# Gain_HPF.net
KiCad netlist of a schematic drawn in EAGLE
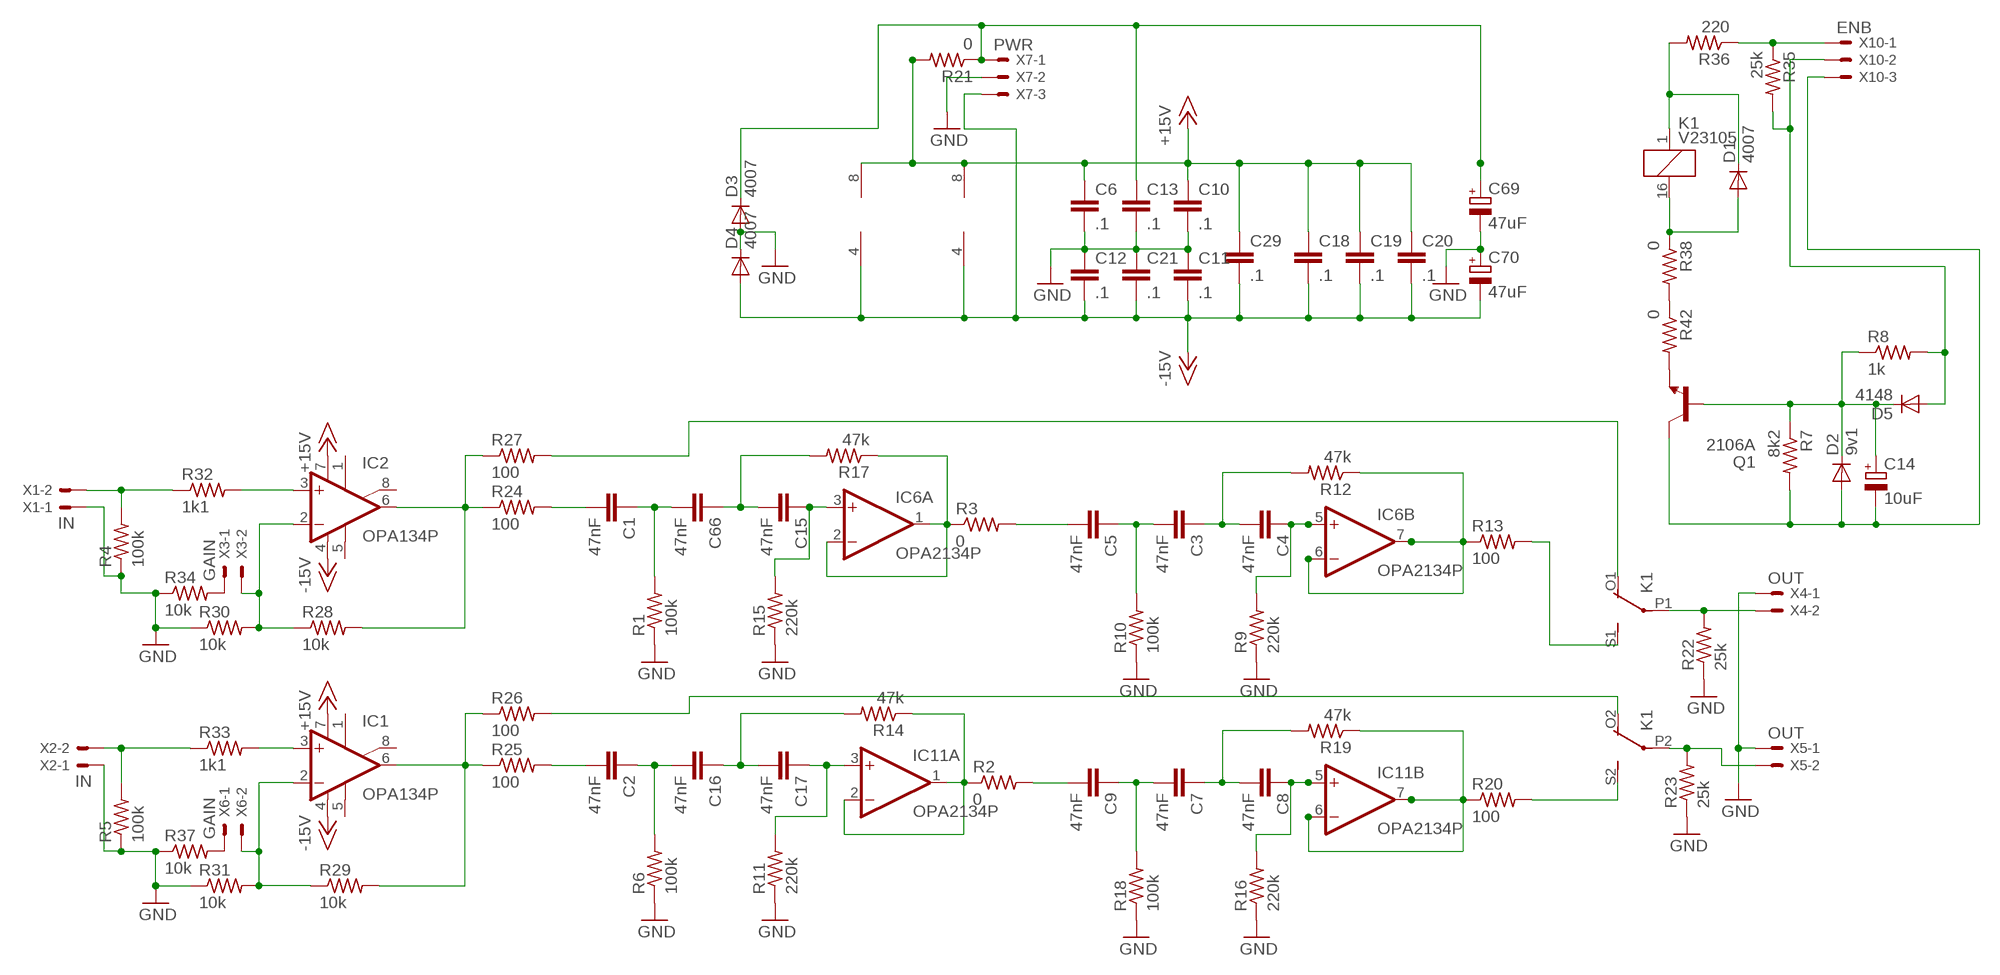
[diagram p0: schematic, sheet 1]

(export (version "E")
  (design (tool "Eeschema 10.0.6"))
  (components
    (comp (ref "C1")
      (value "47nF")
      (footprint "eagle-import:C050-075X075")
      (libsource (lib "eagle-import") (part "C-EU050-075X075"))
    )
    (comp (ref "C2")
      (value "47nF")
      (footprint "eagle-import:C050-075X075")
      (libsource (lib "eagle-import") (part "C-EU050-075X075"))
    )
    (comp (ref "C3")
      (value "47nF")
      (footprint "eagle-import:C050-075X075")
      (libsource (lib "eagle-import") (part "C-EU050-075X075"))
    )
    (comp (ref "C4")
      (value "47nF")
      (footprint "eagle-import:C050-075X075")
      (libsource (lib "eagle-import") (part "C-EU050-075X075"))
    )
    (comp (ref "C5")
      (value "47nF")
      (footprint "eagle-import:C050-075X075")
      (libsource (lib "eagle-import") (part "C-EU050-075X075"))
    )
    (comp (ref "C6")
      (value ".1")
      (footprint "eagle-import:C4532")
      (libsource (lib "eagle-import") (part "C-EUC4532"))
    )
    (comp (ref "C7")
      (value "47nF")
      (footprint "eagle-import:C050-075X075")
      (libsource (lib "eagle-import") (part "C-EU050-075X075"))
    )
    (comp (ref "C8")
      (value "47nF")
      (footprint "eagle-import:C050-075X075")
      (libsource (lib "eagle-import") (part "C-EU050-075X075"))
    )
    (comp (ref "C9")
      (value "47nF")
      (footprint "eagle-import:C050-075X075")
      (libsource (lib "eagle-import") (part "C-EU050-075X075"))
    )
    (comp (ref "C10")
      (value ".1")
      (footprint "eagle-import:C4532")
      (libsource (lib "eagle-import") (part "C-EUC4532"))
    )
    (comp (ref "C11")
      (value ".1")
      (footprint "eagle-import:C4532")
      (libsource (lib "eagle-import") (part "C-EUC4532"))
    )
    (comp (ref "C12")
      (value ".1")
      (footprint "eagle-import:C4532")
      (libsource (lib "eagle-import") (part "C-EUC4532"))
    )
    (comp (ref "C13")
      (value ".1")
      (footprint "eagle-import:C4532")
      (libsource (lib "eagle-import") (part "C-EUC4532"))
    )
    (comp (ref "C14")
      (value "10uF")
      (footprint "eagle-import:E2,5-6")
      (libsource (lib "eagle-import") (part "CPOL-EUE2.5-6"))
    )
    (comp (ref "C15")
      (value "47nF")
      (footprint "eagle-import:C050-075X075")
      (libsource (lib "eagle-import") (part "C-EU050-075X075"))
    )
    (comp (ref "C16")
      (value "47nF")
      (footprint "eagle-import:C050-075X075")
      (libsource (lib "eagle-import") (part "C-EU050-075X075"))
    )
    (comp (ref "C17")
      (value "47nF")
      (footprint "eagle-import:C050-075X075")
      (libsource (lib "eagle-import") (part "C-EU050-075X075"))
    )
    (comp (ref "C18")
      (value ".1")
      (footprint "eagle-import:C4532")
      (libsource (lib "eagle-import") (part "C-EUC4532"))
    )
    (comp (ref "C19")
      (value ".1")
      (footprint "eagle-import:C4532")
      (libsource (lib "eagle-import") (part "C-EUC4532"))
    )
    (comp (ref "C20")
      (value ".1")
      (footprint "eagle-import:C4532")
      (libsource (lib "eagle-import") (part "C-EUC4532"))
    )
    (comp (ref "C21")
      (value ".1")
      (footprint "eagle-import:C4532")
      (libsource (lib "eagle-import") (part "C-EUC4532"))
    )
    (comp (ref "C29")
      (value ".1")
      (footprint "eagle-import:C4532")
      (libsource (lib "eagle-import") (part "C-EUC4532"))
    )
    (comp (ref "C66")
      (value "47nF")
      (footprint "eagle-import:C050-075X075")
      (libsource (lib "eagle-import") (part "C-EU050-075X075"))
    )
    (comp (ref "C69")
      (value "47uF")
      (footprint "eagle-import:E2,5-7")
      (libsource (lib "eagle-import") (part "CPOL-EUE2.5-7"))
    )
    (comp (ref "C70")
      (value "47uF")
      (footprint "eagle-import:E2,5-7")
      (libsource (lib "eagle-import") (part "CPOL-EUE2.5-7"))
    )
    (comp (ref "D1")
      (value "4007")
      (footprint "eagle-import:DO35-7")
      (libsource (lib "eagle-import") (part "1N4148DO35-7"))
    )
    (comp (ref "D2")
      (value "9v1")
      (footprint "eagle-import:DO35-7")
      (libsource (lib "eagle-import") (part "1N4148DO35-7"))
    )
    (comp (ref "D3")
      (value "4007")
      (footprint "eagle-import:DO35-10")
      (libsource (lib "eagle-import") (part "1N4148DO35-10"))
    )
    (comp (ref "D4")
      (value "4007")
      (footprint "eagle-import:DO35-10")
      (libsource (lib "eagle-import") (part "1N4148DO35-10"))
    )
    (comp (ref "D5")
      (value "4148")
      (footprint "eagle-import:DO35-7")
      (libsource (lib "eagle-import") (part "1N4148DO35-7"))
    )
    (comp (ref "IC1")
      (value "OPA134P")
      (footprint "eagle-import:DIL08")
      (libsource (lib "eagle-import") (part "OPA134P"))
    )
    (comp (ref "IC2")
      (value "OPA134P")
      (footprint "eagle-import:DIL08")
      (libsource (lib "eagle-import") (part "OPA134P"))
    )
    (comp (ref "IC6")
      (value "OPA2134P")
      (footprint "eagle-import:DIL08")
      (libsource (lib "eagle-import") (part "OPA2134P"))
    )
    (comp (ref "IC11")
      (value "OPA2134P")
      (footprint "eagle-import:DIL08")
      (libsource (lib "eagle-import") (part "OPA2134P"))
    )
    (comp (ref "K1")
      (value "V23105")
      (footprint "eagle-import:351")
      (libsource (lib "eagle-import") (part "351"))
    )
    (comp (ref "Q1")
      (value "2106A")
      (footprint "eagle-import:TO92-EBC")
      (libsource (lib "eagle-import") (part "BC546B"))
    )
    (comp (ref "R1")
      (value "100k")
      (footprint "eagle-import:0309_10")
      (libsource (lib "eagle-import") (part "R-US_0309/10"))
    )
    (comp (ref "R2")
      (value "0")
      (footprint "eagle-import:0309_10")
      (libsource (lib "eagle-import") (part "R-US_0309/10"))
    )
    (comp (ref "R3")
      (value "0")
      (footprint "eagle-import:0309_12")
      (libsource (lib "eagle-import") (part "R-US_0309/12"))
    )
    (comp (ref "R4")
      (value "100k")
      (footprint "eagle-import:0309_12")
      (libsource (lib "eagle-import") (part "R-US_0309/12"))
    )
    (comp (ref "R5")
      (value "100k")
      (footprint "eagle-import:0309_12")
      (libsource (lib "eagle-import") (part "R-US_0309/12"))
    )
    (comp (ref "R6")
      (value "100k")
      (footprint "eagle-import:0309_10")
      (libsource (lib "eagle-import") (part "R-US_0309/10"))
    )
    (comp (ref "R7")
      (value "8k2")
      (footprint "eagle-import:R1210")
      (libsource (lib "eagle-import") (part "R-US_R1210"))
    )
    (comp (ref "R8")
      (value "1k")
      (footprint "eagle-import:R1210")
      (libsource (lib "eagle-import") (part "R-US_R1210"))
    )
    (comp (ref "R9")
      (value "220k")
      (footprint "eagle-import:0309_10")
      (libsource (lib "eagle-import") (part "R-US_0309/10"))
    )
    (comp (ref "R10")
      (value "100k")
      (footprint "eagle-import:0309_10")
      (libsource (lib "eagle-import") (part "R-US_0309/10"))
    )
    (comp (ref "R11")
      (value "220k")
      (footprint "eagle-import:0309_10")
      (libsource (lib "eagle-import") (part "R-US_0309/10"))
    )
    (comp (ref "R12")
      (value "47k")
      (footprint "eagle-import:0309_10")
      (libsource (lib "eagle-import") (part "R-US_0309/10"))
    )
    (comp (ref "R13")
      (value "100")
      (footprint "eagle-import:0309_10")
      (libsource (lib "eagle-import") (part "R-US_0309/10"))
    )
    (comp (ref "R14")
      (value "47k")
      (footprint "eagle-import:0309_10")
      (libsource (lib "eagle-import") (part "R-US_0309/10"))
    )
    (comp (ref "R15")
      (value "220k")
      (footprint "eagle-import:0309_10")
      (libsource (lib "eagle-import") (part "R-US_0309/10"))
    )
    (comp (ref "R16")
      (value "220k")
      (footprint "eagle-import:0309_10")
      (libsource (lib "eagle-import") (part "R-US_0309/10"))
    )
    (comp (ref "R17")
      (value "47k")
      (footprint "eagle-import:0309_10")
      (libsource (lib "eagle-import") (part "R-US_0309/10"))
    )
    (comp (ref "R18")
      (value "100k")
      (footprint "eagle-import:0309_10")
      (libsource (lib "eagle-import") (part "R-US_0309/10"))
    )
    (comp (ref "R19")
      (value "47k")
      (footprint "eagle-import:0309_10")
      (libsource (lib "eagle-import") (part "R-US_0309/10"))
    )
    (comp (ref "R20")
      (value "100")
      (footprint "eagle-import:0309_10")
      (libsource (lib "eagle-import") (part "R-US_0309/10"))
    )
    (comp (ref "R21")
      (value "0")
      (footprint "eagle-import:0309_10")
      (libsource (lib "eagle-import") (part "R-US_0309/10"))
    )
    (comp (ref "R22")
      (value "25k")
      (footprint "eagle-import:0309_10")
      (libsource (lib "eagle-import") (part "R-US_0309/10"))
    )
    (comp (ref "R23")
      (value "25k")
      (footprint "eagle-import:0309_10")
      (libsource (lib "eagle-import") (part "R-US_0309/10"))
    )
    (comp (ref "R24")
      (value "100")
      (footprint "eagle-import:0309_12")
      (libsource (lib "eagle-import") (part "R-US_0309/12"))
    )
    (comp (ref "R25")
      (value "100")
      (footprint "eagle-import:0309_12")
      (libsource (lib "eagle-import") (part "R-US_0309/12"))
    )
    (comp (ref "R26")
      (value "100")
      (footprint "eagle-import:0309_10")
      (libsource (lib "eagle-import") (part "R-US_0309/10"))
    )
    (comp (ref "R27")
      (value "100")
      (footprint "eagle-import:0309_10")
      (libsource (lib "eagle-import") (part "R-US_0309/10"))
    )
    (comp (ref "R28")
      (value "10k")
      (footprint "eagle-import:0309_10")
      (libsource (lib "eagle-import") (part "R-US_0309/10"))
    )
    (comp (ref "R29")
      (value "10k")
      (footprint "eagle-import:0309_10")
      (libsource (lib "eagle-import") (part "R-US_0309/10"))
    )
    (comp (ref "R30")
      (value "10k")
      (footprint "eagle-import:0309_10")
      (libsource (lib "eagle-import") (part "R-US_0309/10"))
    )
    (comp (ref "R31")
      (value "10k")
      (footprint "eagle-import:0309_10")
      (libsource (lib "eagle-import") (part "R-US_0309/10"))
    )
    (comp (ref "R32")
      (value "1k1")
      (footprint "eagle-import:0309_10")
      (libsource (lib "eagle-import") (part "R-US_0309/10"))
    )
    (comp (ref "R33")
      (value "1k1")
      (footprint "eagle-import:0309_10")
      (libsource (lib "eagle-import") (part "R-US_0309/10"))
    )
    (comp (ref "R34")
      (value "10k")
      (footprint "eagle-import:0309_10")
      (libsource (lib "eagle-import") (part "R-US_0309/10"))
    )
    (comp (ref "R35")
      (value "25k")
      (footprint "eagle-import:0309_10")
      (libsource (lib "eagle-import") (part "R-US_0309/10"))
    )
    (comp (ref "R36")
      (value "220")
      (footprint "eagle-import:0309_10")
      (libsource (lib "eagle-import") (part "R-US_0309/10"))
    )
    (comp (ref "R37")
      (value "10k")
      (footprint "eagle-import:0309_10")
      (libsource (lib "eagle-import") (part "R-US_0309/10"))
    )
    (comp (ref "R38")
      (value "0")
      (footprint "eagle-import:0309_10")
      (libsource (lib "eagle-import") (part "R-US_0309/10"))
    )
    (comp (ref "R42")
      (value "0")
      (footprint "eagle-import:0309_10")
      (libsource (lib "eagle-import") (part "R-US_0309/10"))
    )
    (comp (ref "X1")
      (value "IN")
      (footprint "eagle-import:22-23-2021")
      (fields (field (name "MF") "MOLEX") (field (name "MPN") "22-23-2021"))
      (libsource (lib "eagle-import") (part "22-23-2021"))
    )
    (comp (ref "X2")
      (value "IN")
      (footprint "eagle-import:22-23-2021")
      (fields (field (name "MF") "MOLEX") (field (name "MPN") "22-23-2021"))
      (libsource (lib "eagle-import") (part "22-23-2021"))
    )
    (comp (ref "X3")
      (value "GAIN")
      (footprint "eagle-import:22-23-2021")
      (fields (field (name "MF") "MOLEX") (field (name "MPN") "22-23-2021"))
      (libsource (lib "eagle-import") (part "22-23-2021"))
    )
    (comp (ref "X4")
      (value "OUT")
      (footprint "eagle-import:22-23-2021")
      (fields (field (name "MF") "MOLEX") (field (name "MPN") "22-23-2021"))
      (libsource (lib "eagle-import") (part "22-23-2021"))
    )
    (comp (ref "X5")
      (value "OUT")
      (footprint "eagle-import:22-23-2021")
      (fields (field (name "MF") "MOLEX") (field (name "MPN") "22-23-2021"))
      (libsource (lib "eagle-import") (part "22-23-2021"))
    )
    (comp (ref "X6")
      (value "GAIN")
      (footprint "eagle-import:22-23-2021")
      (fields (field (name "MF") "MOLEX") (field (name "MPN") "22-23-2021"))
      (libsource (lib "eagle-import") (part "22-23-2021"))
    )
    (comp (ref "X7")
      (value "PWR")
      (footprint "eagle-import:22-23-2031")
      (fields (field (name "MF") "MOLEX") (field (name "MPN") "22-23-2031"))
      (libsource (lib "eagle-import") (part "22-23-2031"))
    )
    (comp (ref "X10")
      (value "ENB")
      (footprint "eagle-import:22-23-2031")
      (fields (field (name "MF") "MOLEX") (field (name "MPN") "22-23-2031"))
      (libsource (lib "eagle-import") (part "22-23-2031"))
    )
  )
  (nets
    (net (code "1") (name "+15V") (class "Default")
      (node (ref "C10") (pin "1") (pinfunction "1_1") (pintype "passive"))
      (node (ref "C18") (pin "1") (pinfunction "1_1") (pintype "passive"))
      (node (ref "C19") (pin "1") (pinfunction "1_1") (pintype "passive"))
      (node (ref "C20") (pin "1") (pinfunction "1_1") (pintype "passive"))
      (node (ref "C29") (pin "1") (pinfunction "1_1") (pintype "passive"))
      (node (ref "C6") (pin "1") (pinfunction "1_1") (pintype "passive"))
      (node (ref "IC1") (pin "7") (pinfunction "V+_7") (pintype "power_in"))
      (node (ref "IC11") (pin "8") (pinfunction "V+_8") (pintype "power_in"))
      (node (ref "IC2") (pin "7") (pinfunction "V+_7") (pintype "power_in"))
      (node (ref "IC6") (pin "8") (pinfunction "V+_8") (pintype "power_in"))
      (node (ref "R21") (pin "2") (pinfunction "2_2") (pintype "passive"))
    )
    (net (code "2") (name "-15V") (class "Default")
      (node (ref "C11") (pin "2") (pinfunction "2_2") (pintype "passive"))
      (node (ref "C12") (pin "2") (pinfunction "2_2") (pintype "passive"))
      (node (ref "C18") (pin "2") (pinfunction "2_2") (pintype "passive"))
      (node (ref "C19") (pin "2") (pinfunction "2_2") (pintype "passive"))
      (node (ref "C20") (pin "2") (pinfunction "2_2") (pintype "passive"))
      (node (ref "C21") (pin "2") (pinfunction "2_2") (pintype "passive"))
      (node (ref "C29") (pin "2") (pinfunction "2_2") (pintype "passive"))
      (node (ref "C70") (pin "-") (pinfunction "-_-") (pintype "passive"))
      (node (ref "D4") (pin "A") (pinfunction "A_A") (pintype "passive"))
      (node (ref "IC1") (pin "4") (pinfunction "V-_4") (pintype "power_in"))
      (node (ref "IC11") (pin "4") (pinfunction "V-_4") (pintype "power_in"))
      (node (ref "IC2") (pin "4") (pinfunction "V-_4") (pintype "power_in"))
      (node (ref "IC6") (pin "4") (pinfunction "V-_4") (pintype "power_in"))
      (node (ref "X7") (pin "3") (pinfunction "S_3") (pintype "passive"))
    )
    (net (code "3") (name "GND") (class "Default")
      (node (ref "C10") (pin "2") (pinfunction "2_2") (pintype "passive"))
      (node (ref "C11") (pin "1") (pinfunction "1_1") (pintype "passive"))
      (node (ref "C12") (pin "1") (pinfunction "1_1") (pintype "passive"))
      (node (ref "C13") (pin "2") (pinfunction "2_2") (pintype "passive"))
      (node (ref "C21") (pin "1") (pinfunction "1_1") (pintype "passive"))
      (node (ref "C6") (pin "2") (pinfunction "2_2") (pintype "passive"))
      (node (ref "C69") (pin "-") (pinfunction "-_-") (pintype "passive"))
      (node (ref "C70") (pin "+") (pinfunction "+_+") (pintype "passive"))
      (node (ref "D3") (pin "A") (pinfunction "A_A") (pintype "passive"))
      (node (ref "D4") (pin "C") (pinfunction "C_C") (pintype "passive"))
      (node (ref "R1") (pin "1") (pinfunction "1_1") (pintype "passive"))
      (node (ref "R10") (pin "1") (pinfunction "1_1") (pintype "passive"))
      (node (ref "R11") (pin "1") (pinfunction "1_1") (pintype "passive"))
      (node (ref "R15") (pin "1") (pinfunction "1_1") (pintype "passive"))
      (node (ref "R16") (pin "1") (pinfunction "1_1") (pintype "passive"))
      (node (ref "R18") (pin "1") (pinfunction "1_1") (pintype "passive"))
      (node (ref "R22") (pin "1") (pinfunction "1_1") (pintype "passive"))
      (node (ref "R23") (pin "1") (pinfunction "1_1") (pintype "passive"))
      (node (ref "R30") (pin "1") (pinfunction "1_1") (pintype "passive"))
      (node (ref "R31") (pin "1") (pinfunction "1_1") (pintype "passive"))
      (node (ref "R34") (pin "1") (pinfunction "1_1") (pintype "passive"))
      (node (ref "R37") (pin "1") (pinfunction "1_1") (pintype "passive"))
      (node (ref "R4") (pin "1") (pinfunction "1_1") (pintype "passive"))
      (node (ref "R5") (pin "1") (pinfunction "1_1") (pintype "passive"))
      (node (ref "R6") (pin "1") (pinfunction "1_1") (pintype "passive"))
      (node (ref "R9") (pin "1") (pinfunction "1_1") (pintype "passive"))
      (node (ref "X1") (pin "1") (pinfunction "S_1") (pintype "passive"))
      (node (ref "X2") (pin "1") (pinfunction "S_1") (pintype "passive"))
      (node (ref "X4") (pin "1") (pinfunction "S_1") (pintype "passive"))
      (node (ref "X5") (pin "1") (pinfunction "S_1") (pintype "passive"))
      (node (ref "X7") (pin "2") (pinfunction "S_2") (pintype "passive"))
    )
    (net (code "4") (name "Net-(C1-Pad1)") (class "Default")
      (node (ref "C1") (pin "1") (pinfunction "1_1") (pintype "passive"))
      (node (ref "C66") (pin "2") (pinfunction "2_2") (pintype "passive"))
      (node (ref "R1") (pin "2") (pinfunction "2_2") (pintype "passive"))
    )
    (net (code "5") (name "Net-(C1-Pad2)") (class "Default")
      (node (ref "C1") (pin "2") (pinfunction "2_2") (pintype "passive"))
      (node (ref "R24") (pin "2") (pinfunction "2_2") (pintype "passive"))
    )
    (net (code "6") (name "Net-(C2-Pad2)") (class "Default")
      (node (ref "C2") (pin "2") (pinfunction "2_2") (pintype "passive"))
      (node (ref "R25") (pin "2") (pinfunction "2_2") (pintype "passive"))
    )
    (net (code "7") (name "Net-(C3-Pad1)") (class "Default")
      (node (ref "C3") (pin "1") (pinfunction "1_1") (pintype "passive"))
      (node (ref "C4") (pin "2") (pinfunction "2_2") (pintype "passive"))
      (node (ref "R12") (pin "2") (pinfunction "2_2") (pintype "passive"))
    )
    (net (code "8") (name "Net-(C3-Pad2)") (class "Default")
      (node (ref "C3") (pin "2") (pinfunction "2_2") (pintype "passive"))
      (node (ref "C5") (pin "1") (pinfunction "1_1") (pintype "passive"))
      (node (ref "R10") (pin "2") (pinfunction "2_2") (pintype "passive"))
    )
    (net (code "9") (name "Net-(C5-Pad2)") (class "Default")
      (node (ref "C5") (pin "2") (pinfunction "2_2") (pintype "passive"))
      (node (ref "R3") (pin "2") (pinfunction "2_2") (pintype "passive"))
    )
    (net (code "10") (name "Net-(C7-Pad1)") (class "Default")
      (node (ref "C7") (pin "1") (pinfunction "1_1") (pintype "passive"))
      (node (ref "C8") (pin "2") (pinfunction "2_2") (pintype "passive"))
      (node (ref "R19") (pin "2") (pinfunction "2_2") (pintype "passive"))
    )
    (net (code "11") (name "Net-(C7-Pad2)") (class "Default")
      (node (ref "C7") (pin "2") (pinfunction "2_2") (pintype "passive"))
      (node (ref "C9") (pin "1") (pinfunction "1_1") (pintype "passive"))
      (node (ref "R18") (pin "2") (pinfunction "2_2") (pintype "passive"))
    )
    (net (code "12") (name "Net-(C9-Pad2)") (class "Default")
      (node (ref "C9") (pin "2") (pinfunction "2_2") (pintype "passive"))
      (node (ref "R2") (pin "2") (pinfunction "2_2") (pintype "passive"))
    )
    (net (code "13") (name "Net-(C14-Pad+)") (class "Default")
      (node (ref "C14") (pin "+") (pinfunction "+_+") (pintype "passive"))
      (node (ref "D2") (pin "C") (pinfunction "C_C") (pintype "passive"))
      (node (ref "D5") (pin "C") (pinfunction "C_C") (pintype "passive"))
      (node (ref "Q1") (pin "B") (pinfunction "B_B") (pintype "passive"))
      (node (ref "R7") (pin "1") (pinfunction "1_1") (pintype "passive"))
      (node (ref "R8") (pin "1") (pinfunction "1_1") (pintype "passive"))
    )
    (net (code "14") (name "Net-(C15-Pad2)") (class "Default")
      (node (ref "C15") (pin "2") (pinfunction "2_2") (pintype "passive"))
      (node (ref "C66") (pin "1") (pinfunction "1_1") (pintype "passive"))
      (node (ref "R17") (pin "2") (pinfunction "2_2") (pintype "passive"))
    )
    (net (code "15") (name "Net-(C16-Pad1)") (class "Default")
      (node (ref "C16") (pin "1") (pinfunction "1_1") (pintype "passive"))
      (node (ref "C17") (pin "2") (pinfunction "2_2") (pintype "passive"))
      (node (ref "R14") (pin "2") (pinfunction "2_2") (pintype "passive"))
    )
    (net (code "16") (name "Net-(C16-Pad2)") (class "Default")
      (node (ref "C16") (pin "2") (pinfunction "2_2") (pintype "passive"))
      (node (ref "C2") (pin "1") (pinfunction "1_1") (pintype "passive"))
      (node (ref "R6") (pin "2") (pinfunction "2_2") (pintype "passive"))
    )
    (net (code "17") (name "Net-(D1-PadC)") (class "Default")
      (node (ref "D1") (pin "C") (pinfunction "C_C") (pintype "passive"))
      (node (ref "K1") (pin "1") (pinfunction "1_1") (pintype "passive"))
      (node (ref "R36") (pin "2") (pinfunction "2_2") (pintype "passive"))
    )
    (net (code "18") (name "Net-(IC1-+IN)") (class "Default")
      (node (ref "IC1") (pin "3") (pinfunction "+IN_3") (pintype "input"))
      (node (ref "R33") (pin "2") (pinfunction "2_2") (pintype "passive"))
    )
    (net (code "19") (name "Net-(IC1--IN)") (class "Default")
      (node (ref "IC1") (pin "2") (pinfunction "-IN_2") (pintype "input"))
      (node (ref "R29") (pin "1") (pinfunction "1_1") (pintype "passive"))
      (node (ref "R31") (pin "2") (pinfunction "2_2") (pintype "passive"))
      (node (ref "X6") (pin "2") (pinfunction "S_2") (pintype "passive"))
    )
    (net (code "20") (name "Net-(IC1-OUT)") (class "Default")
      (node (ref "IC1") (pin "6") (pinfunction "OUT_6") (pintype "output"))
      (node (ref "R25") (pin "1") (pinfunction "1_1") (pintype "passive"))
      (node (ref "R26") (pin "1") (pinfunction "1_1") (pintype "passive"))
      (node (ref "R29") (pin "2") (pinfunction "2_2") (pintype "passive"))
    )
    (net (code "21") (name "Net-(IC2-+IN)") (class "Default")
      (node (ref "IC2") (pin "3") (pinfunction "+IN_3") (pintype "input"))
      (node (ref "R32") (pin "2") (pinfunction "2_2") (pintype "passive"))
    )
    (net (code "22") (name "Net-(IC2--IN)") (class "Default")
      (node (ref "IC2") (pin "2") (pinfunction "-IN_2") (pintype "input"))
      (node (ref "R28") (pin "1") (pinfunction "1_1") (pintype "passive"))
      (node (ref "R30") (pin "2") (pinfunction "2_2") (pintype "passive"))
      (node (ref "X3") (pin "2") (pinfunction "S_2") (pintype "passive"))
    )
    (net (code "23") (name "Net-(IC2-OUT)") (class "Default")
      (node (ref "IC2") (pin "6") (pinfunction "OUT_6") (pintype "output"))
      (node (ref "R24") (pin "1") (pinfunction "1_1") (pintype "passive"))
      (node (ref "R27") (pin "1") (pinfunction "1_1") (pintype "passive"))
      (node (ref "R28") (pin "2") (pinfunction "2_2") (pintype "passive"))
    )
    (net (code "24") (name "Net-(IC6A-+IN)") (class "Default")
      (node (ref "C15") (pin "1") (pinfunction "1_1") (pintype "passive"))
      (node (ref "IC6") (pin "3") (pinfunction "+IN_3") (pintype "input"))
      (node (ref "R15") (pin "2") (pinfunction "2_2") (pintype "passive"))
    )
    (net (code "25") (name "Net-(IC6A--IN)") (class "Default")
      (node (ref "IC6") (pin "1") (pinfunction "OUT_1") (pintype "output"))
      (node (ref "IC6") (pin "2") (pinfunction "-IN_2") (pintype "input"))
      (node (ref "R17") (pin "1") (pinfunction "1_1") (pintype "passive"))
      (node (ref "R3") (pin "1") (pinfunction "1_1") (pintype "passive"))
    )
    (net (code "26") (name "Net-(IC6B-+IN)") (class "Default")
      (node (ref "C4") (pin "1") (pinfunction "1_1") (pintype "passive"))
      (node (ref "IC6") (pin "5") (pinfunction "+IN_5") (pintype "input"))
      (node (ref "R9") (pin "2") (pinfunction "2_2") (pintype "passive"))
    )
    (net (code "27") (name "Net-(IC6B--IN)") (class "Default")
      (node (ref "IC6") (pin "6") (pinfunction "-IN_6") (pintype "input"))
      (node (ref "IC6") (pin "7") (pinfunction "OUT_7") (pintype "output"))
      (node (ref "R12") (pin "1") (pinfunction "1_1") (pintype "passive"))
      (node (ref "R13") (pin "1") (pinfunction "1_1") (pintype "passive"))
    )
    (net (code "28") (name "Net-(IC11A-+IN)") (class "Default")
      (node (ref "C17") (pin "1") (pinfunction "1_1") (pintype "passive"))
      (node (ref "IC11") (pin "3") (pinfunction "+IN_3") (pintype "input"))
      (node (ref "R11") (pin "2") (pinfunction "2_2") (pintype "passive"))
    )
    (net (code "29") (name "Net-(IC11A--IN)") (class "Default")
      (node (ref "IC11") (pin "1") (pinfunction "OUT_1") (pintype "output"))
      (node (ref "IC11") (pin "2") (pinfunction "-IN_2") (pintype "input"))
      (node (ref "R14") (pin "1") (pinfunction "1_1") (pintype "passive"))
      (node (ref "R2") (pin "1") (pinfunction "1_1") (pintype "passive"))
    )
    (net (code "30") (name "Net-(IC11B-+IN)") (class "Default")
      (node (ref "C8") (pin "1") (pinfunction "1_1") (pintype "passive"))
      (node (ref "IC11") (pin "5") (pinfunction "+IN_5") (pintype "input"))
      (node (ref "R16") (pin "2") (pinfunction "2_2") (pintype "passive"))
    )
    (net (code "31") (name "Net-(IC11B--IN)") (class "Default")
      (node (ref "IC11") (pin "6") (pinfunction "-IN_6") (pintype "input"))
      (node (ref "IC11") (pin "7") (pinfunction "OUT_7") (pintype "output"))
      (node (ref "R19") (pin "1") (pinfunction "1_1") (pintype "passive"))
      (node (ref "R20") (pin "1") (pinfunction "1_1") (pintype "passive"))
    )
    (net (code "32") (name "Net-(K1A-2)") (class "Default")
      (node (ref "D1") (pin "A") (pinfunction "A_A") (pintype "passive"))
      (node (ref "K1") (pin "16") (pinfunction "2_16") (pintype "passive"))
      (node (ref "R38") (pin "1") (pinfunction "1_1") (pintype "passive"))
    )
    (net (code "33") (name "Net-(K1B-O)") (class "Default")
      (node (ref "K1") (pin "O1") (pinfunction "O_O1") (pintype "passive"))
      (node (ref "R27") (pin "2") (pinfunction "2_2") (pintype "passive"))
    )
    (net (code "34") (name "Net-(K1B-P)") (class "Default")
      (node (ref "K1") (pin "P1") (pinfunction "P_P1") (pintype "passive"))
      (node (ref "R22") (pin "2") (pinfunction "2_2") (pintype "passive"))
      (node (ref "X4") (pin "2") (pinfunction "S_2") (pintype "passive"))
    )
    (net (code "35") (name "Net-(K1B-S)") (class "Default")
      (node (ref "K1") (pin "S1") (pinfunction "S_S1") (pintype "passive"))
      (node (ref "R13") (pin "2") (pinfunction "2_2") (pintype "passive"))
    )
    (net (code "36") (name "Net-(K1C-O)") (class "Default")
      (node (ref "K1") (pin "O2") (pinfunction "O_O2") (pintype "passive"))
      (node (ref "R26") (pin "2") (pinfunction "2_2") (pintype "passive"))
    )
    (net (code "37") (name "Net-(K1C-P)") (class "Default")
      (node (ref "K1") (pin "P2") (pinfunction "P_P2") (pintype "passive"))
      (node (ref "R23") (pin "2") (pinfunction "2_2") (pintype "passive"))
      (node (ref "X5") (pin "2") (pinfunction "S_2") (pintype "passive"))
    )
    (net (code "38") (name "Net-(K1C-S)") (class "Default")
      (node (ref "K1") (pin "S2") (pinfunction "S_S2") (pintype "passive"))
      (node (ref "R20") (pin "2") (pinfunction "2_2") (pintype "passive"))
    )
    (net (code "39") (name "Net-(Q1-PadE)") (class "Default")
      (node (ref "Q1") (pin "E") (pinfunction "E_E") (pintype "passive"))
      (node (ref "R42") (pin "2") (pinfunction "2_2") (pintype "passive"))
    )
    (net (code "40") (name "Net-(R38-Pad2)") (class "Default")
      (node (ref "R38") (pin "2") (pinfunction "2_2") (pintype "passive"))
      (node (ref "R42") (pin "1") (pinfunction "1_1") (pintype "passive"))
    )
    (net (code "41") (name "Net-(X1B-S)") (class "Default")
      (node (ref "R32") (pin "1") (pinfunction "1_1") (pintype "passive"))
      (node (ref "R4") (pin "2") (pinfunction "2_2") (pintype "passive"))
      (node (ref "X1") (pin "2") (pinfunction "S_2") (pintype "passive"))
    )
    (net (code "42") (name "Net-(X2B-S)") (class "Default")
      (node (ref "R33") (pin "1") (pinfunction "1_1") (pintype "passive"))
      (node (ref "R5") (pin "2") (pinfunction "2_2") (pintype "passive"))
      (node (ref "X2") (pin "2") (pinfunction "S_2") (pintype "passive"))
    )
    (net (code "43") (name "Net-(X3A-S)") (class "Default")
      (node (ref "R34") (pin "2") (pinfunction "2_2") (pintype "passive"))
      (node (ref "X3") (pin "1") (pinfunction "S_1") (pintype "passive"))
    )
    (net (code "44") (name "Net-(X6A-S)") (class "Default")
      (node (ref "R37") (pin "2") (pinfunction "2_2") (pintype "passive"))
      (node (ref "X6") (pin "1") (pinfunction "S_1") (pintype "passive"))
    )
    (net (code "45") (name "Net-(X7A-S)") (class "Default")
      (node (ref "C13") (pin "1") (pinfunction "1_1") (pintype "passive"))
      (node (ref "C69") (pin "+") (pinfunction "+_+") (pintype "passive"))
      (node (ref "D3") (pin "C") (pinfunction "C_C") (pintype "passive"))
      (node (ref "R21") (pin "1") (pinfunction "1_1") (pintype "passive"))
      (node (ref "X7") (pin "1") (pinfunction "S_1") (pintype "passive"))
    )
    (net (code "46") (name "Net-(X10A-S)") (class "Default")
      (node (ref "R35") (pin "1") (pinfunction "1_1") (pintype "passive"))
      (node (ref "R36") (pin "1") (pinfunction "1_1") (pintype "passive"))
      (node (ref "X10") (pin "1") (pinfunction "S_1") (pintype "passive"))
    )
    (net (code "47") (name "Net-(X10B-S)") (class "Default")
      (node (ref "D5") (pin "A") (pinfunction "A_A") (pintype "passive"))
      (node (ref "R35") (pin "2") (pinfunction "2_2") (pintype "passive"))
      (node (ref "R8") (pin "2") (pinfunction "2_2") (pintype "passive"))
      (node (ref "X10") (pin "2") (pinfunction "S_2") (pintype "passive"))
    )
    (net (code "48") (name "Net-(X10C-S)") (class "Default")
      (node (ref "C14") (pin "-") (pinfunction "-_-") (pintype "passive"))
      (node (ref "D2") (pin "A") (pinfunction "A_A") (pintype "passive"))
      (node (ref "Q1") (pin "C") (pinfunction "C_C") (pintype "passive"))
      (node (ref "R7") (pin "2") (pinfunction "2_2") (pintype "passive"))
      (node (ref "X10") (pin "3") (pinfunction "S_3") (pintype "passive"))
    )
    (net (code "49") (name "unconnected-(IC1-ON1-Pad1)") (class "Default")
      (node (ref "IC1") (pin "1") (pinfunction "ON1_1") (pintype "passive"))
    )
    (net (code "50") (name "unconnected-(IC1-ON2-Pad8)") (class "Default")
      (node (ref "IC1") (pin "8") (pinfunction "ON2_8") (pintype "passive"))
    )
    (net (code "51") (name "unconnected-(IC1-OPT-Pad5)") (class "Default")
      (node (ref "IC1") (pin "5") (pinfunction "OPT_5") (pintype "passive"))
    )
    (net (code "52") (name "unconnected-(IC2-ON1-Pad1)") (class "Default")
      (node (ref "IC2") (pin "1") (pinfunction "ON1_1") (pintype "passive"))
    )
    (net (code "53") (name "unconnected-(IC2-ON2-Pad8)") (class "Default")
      (node (ref "IC2") (pin "8") (pinfunction "ON2_8") (pintype "passive"))
    )
    (net (code "54") (name "unconnected-(IC2-OPT-Pad5)") (class "Default")
      (node (ref "IC2") (pin "5") (pinfunction "OPT_5") (pintype "passive"))
    )
  )
)
